# turbidity_sensor_module.net
KiCad netlist of a schematic drawn in EAGLE
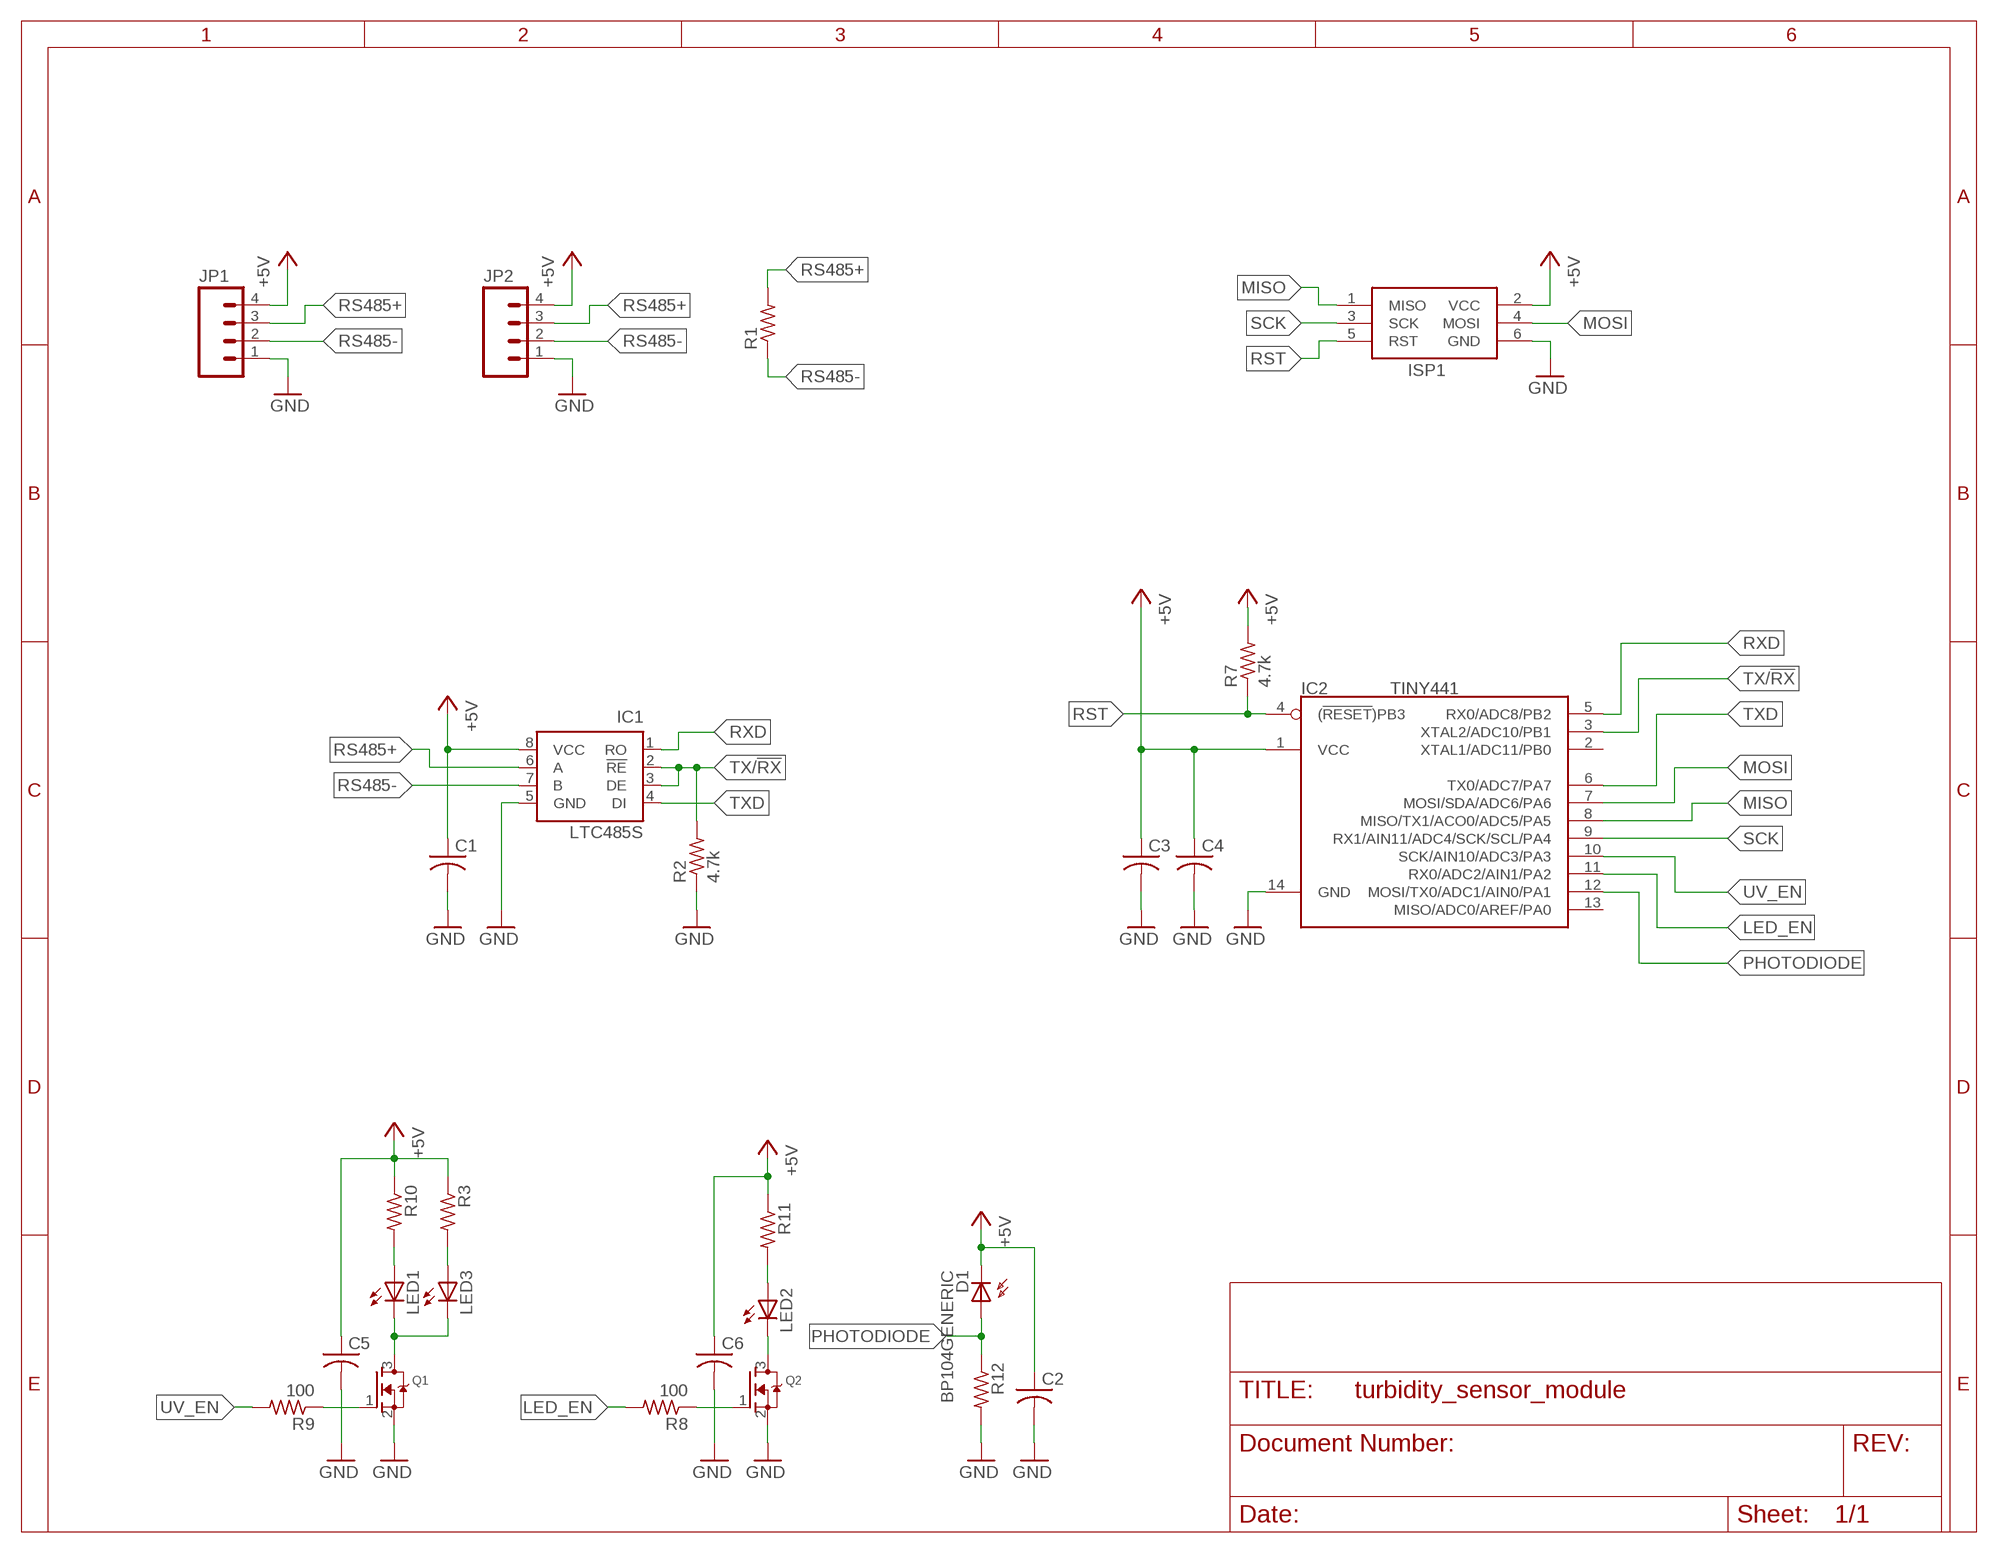
[diagram p0: schematic, sheet 1]

(export (version "E")
  (design (tool "Eeschema 10.0.6"))
  (components
    (comp (ref "C1")
      (value "C-USC1206")
      (footprint "eagle-import:C1206")
      (libsource (lib "eagle-import") (part "C-USC1206"))
    )
    (comp (ref "C2")
      (value "C-USC1206")
      (footprint "eagle-import:C1206")
      (libsource (lib "eagle-import") (part "C-USC1206"))
    )
    (comp (ref "C3")
      (value "C-USC1206")
      (footprint "eagle-import:C1206")
      (libsource (lib "eagle-import") (part "C-USC1206"))
    )
    (comp (ref "C4")
      (value "C-USC1206")
      (footprint "eagle-import:C1206")
      (libsource (lib "eagle-import") (part "C-USC1206"))
    )
    (comp (ref "C5")
      (value "C-USC1206")
      (footprint "eagle-import:C1206")
      (libsource (lib "eagle-import") (part "C-USC1206"))
    )
    (comp (ref "C6")
      (value "C-USC1206")
      (footprint "eagle-import:C1206")
      (libsource (lib "eagle-import") (part "C-USC1206"))
    )
    (comp (ref "D1")
      (value "BP104GENERIC")
      (footprint "eagle-import:PHOTODIODE")
      (libsource (lib "eagle-import") (part "BP104GENERIC"))
    )
    (comp (ref "IC1")
      (value "LTC485S")
      (footprint "eagle-import:SOIC8")
      (libsource (lib "eagle-import") (part "LTC485S"))
    )
    (comp (ref "IC2")
      (value "TINY441")
      (footprint "eagle-import:SOIC14")
      (libsource (lib "eagle-import") (part "TINY441"))
    )
    (comp (ref "ISP1")
      (value "AVRISP-6")
      (footprint "eagle-import:AVRISP")
      (libsource (lib "eagle-import") (part "AVRISP-6"))
    )
    (comp (ref "JP1")
      (value "M04LONGPADS")
      (footprint "eagle-import:1X04_LONGPADS")
      (libsource (lib "eagle-import") (part "M04LONGPADS"))
    )
    (comp (ref "JP2")
      (value "M04LONGPADS")
      (footprint "eagle-import:1X04_LONGPADS")
      (libsource (lib "eagle-import") (part "M04LONGPADS"))
    )
    (comp (ref "LED1")
      (value "LED5MM")
      (footprint "eagle-import:LED5MM")
      (libsource (lib "eagle-import") (part "LED5MM"))
    )
    (comp (ref "LED2")
      (value "LED5MM")
      (footprint "eagle-import:LED5MM")
      (libsource (lib "eagle-import") (part "LED5MM"))
    )
    (comp (ref "LED3")
      (value "LED5MM")
      (footprint "eagle-import:LED5MM")
      (libsource (lib "eagle-import") (part "LED5MM"))
    )
    (comp (ref "Q1")
      (value "MOSFET-NREFLOW")
      (footprint "eagle-import:SOT23")
      (libsource (lib "eagle-import") (part "MOSFET-NREFLOW"))
    )
    (comp (ref "Q2")
      (value "MOSFET-NREFLOW")
      (footprint "eagle-import:SOT23")
      (libsource (lib "eagle-import") (part "MOSFET-NREFLOW"))
    )
    (comp (ref "R1")
      (value "R-US_R1206")
      (footprint "eagle-import:R1206")
      (libsource (lib "eagle-import") (part "R-US_R1206"))
    )
    (comp (ref "R2")
      (value "4.7k")
      (footprint "eagle-import:R1206")
      (libsource (lib "eagle-import") (part "R-US_R1206"))
    )
    (comp (ref "R3")
      (value "R-US_R1206")
      (footprint "eagle-import:R1206")
      (libsource (lib "eagle-import") (part "R-US_R1206"))
    )
    (comp (ref "R7")
      (value "4.7k")
      (footprint "eagle-import:R1206")
      (libsource (lib "eagle-import") (part "R-US_R1206"))
    )
    (comp (ref "R8")
      (value "100")
      (footprint "eagle-import:R1206")
      (libsource (lib "eagle-import") (part "R-US_R1206"))
    )
    (comp (ref "R9")
      (value "100")
      (footprint "eagle-import:R1206")
      (libsource (lib "eagle-import") (part "R-US_R1206"))
    )
    (comp (ref "R10")
      (value "R-US_R1206")
      (footprint "eagle-import:R1206")
      (libsource (lib "eagle-import") (part "R-US_R1206"))
    )
    (comp (ref "R11")
      (value "R-US_R1206")
      (footprint "eagle-import:R1206")
      (libsource (lib "eagle-import") (part "R-US_R1206"))
    )
    (comp (ref "R12")
      (value "R-US_R1206")
      (footprint "eagle-import:R1206")
      (libsource (lib "eagle-import") (part "R-US_R1206"))
    )
  )
  (nets
    (net (code "1") (name "+5V") (class "Default")
      (node (ref "C1") (pin "1") (pinfunction "1_1") (pintype "passive"))
      (node (ref "C2") (pin "1") (pinfunction "1_1") (pintype "passive"))
      (node (ref "C3") (pin "1") (pinfunction "1_1") (pintype "passive"))
      (node (ref "C4") (pin "1") (pinfunction "1_1") (pintype "passive"))
      (node (ref "C5") (pin "1") (pinfunction "1_1") (pintype "passive"))
      (node (ref "C6") (pin "1") (pinfunction "1_1") (pintype "passive"))
      (node (ref "D1") (pin "K") (pinfunction "C_K") (pintype "passive"))
      (node (ref "IC1") (pin "8") (pinfunction "VCC_8") (pintype "input"))
      (node (ref "IC2") (pin "1") (pinfunction "VCC_1") (pintype "power_in"))
      (node (ref "ISP1") (pin "2") (pinfunction "VCC_2") (pintype "power_in"))
      (node (ref "JP1") (pin "4") (pinfunction "4_4") (pintype "passive"))
      (node (ref "JP2") (pin "4") (pinfunction "4_4") (pintype "passive"))
      (node (ref "R10") (pin "1") (pinfunction "1_1") (pintype "passive"))
      (node (ref "R11") (pin "1") (pinfunction "1_1") (pintype "passive"))
      (node (ref "R3") (pin "1") (pinfunction "1_1") (pintype "passive"))
      (node (ref "R7") (pin "2") (pinfunction "2_2") (pintype "passive"))
    )
    (net (code "2") (name "/TX{slash}~{RX}") (class "Default")
      (node (ref "IC1") (pin "2") (pinfunction "~{RE}_2") (pintype "input"))
      (node (ref "IC1") (pin "3") (pinfunction "DE_3") (pintype "input"))
      (node (ref "IC2") (pin "3") (pinfunction "XTAL2/ADC10/PB1_3") (pintype "bidirectional"))
      (node (ref "R2") (pin "2") (pinfunction "2_2") (pintype "passive"))
    )
    (net (code "3") (name "GND") (class "Default")
      (node (ref "C1") (pin "2") (pinfunction "2_2") (pintype "passive"))
      (node (ref "C2") (pin "2") (pinfunction "2_2") (pintype "passive"))
      (node (ref "C3") (pin "2") (pinfunction "2_2") (pintype "passive"))
      (node (ref "C4") (pin "2") (pinfunction "2_2") (pintype "passive"))
      (node (ref "C5") (pin "2") (pinfunction "2_2") (pintype "passive"))
      (node (ref "C6") (pin "2") (pinfunction "2_2") (pintype "passive"))
      (node (ref "IC1") (pin "5") (pinfunction "GND_5") (pintype "input"))
      (node (ref "IC2") (pin "14") (pinfunction "GND_14") (pintype "power_in"))
      (node (ref "ISP1") (pin "6") (pinfunction "GND_6") (pintype "power_in"))
      (node (ref "JP1") (pin "1") (pinfunction "1_1") (pintype "passive"))
      (node (ref "JP2") (pin "1") (pinfunction "1_1") (pintype "passive"))
      (node (ref "Q1") (pin "2") (pinfunction "S_2") (pintype "bidirectional"))
      (node (ref "Q2") (pin "2") (pinfunction "S_2") (pintype "bidirectional"))
      (node (ref "R12") (pin "2") (pinfunction "2_2") (pintype "passive"))
      (node (ref "R2") (pin "1") (pinfunction "1_1") (pintype "passive"))
    )
    (net (code "4") (name "LED_EN") (class "Default")
      (node (ref "IC2") (pin "11") (pinfunction "RX0/ADC2/AIN1/PA2_11") (pintype "bidirectional"))
      (node (ref "R8") (pin "2") (pinfunction "2_2") (pintype "passive"))
    )
    (net (code "5") (name "MISO") (class "Default")
      (node (ref "IC2") (pin "8") (pinfunction "MISO/TX1/ACO0/ADC5/PA5_8") (pintype "bidirectional"))
      (node (ref "ISP1") (pin "1") (pinfunction "MISO_1") (pintype "input"))
    )
    (net (code "6") (name "MOSI") (class "Default")
      (node (ref "IC2") (pin "7") (pinfunction "MOSI/SDA/ADC6/PA6_7") (pintype "bidirectional"))
      (node (ref "ISP1") (pin "4") (pinfunction "MOSI_4") (pintype "output"))
    )
    (net (code "7") (name "Net-(LED1-C)") (class "Default")
      (node (ref "LED1") (pin "K") (pinfunction "C_K") (pintype "passive"))
      (node (ref "LED3") (pin "K") (pinfunction "C_K") (pintype "passive"))
      (node (ref "Q1") (pin "3") (pinfunction "D_3") (pintype "bidirectional"))
    )
    (net (code "8") (name "Net-(LED1-PadA)") (class "Default")
      (node (ref "LED1") (pin "A") (pinfunction "A_A") (pintype "passive"))
      (node (ref "R10") (pin "2") (pinfunction "2_2") (pintype "passive"))
    )
    (net (code "9") (name "Net-(LED2-C)") (class "Default")
      (node (ref "LED2") (pin "K") (pinfunction "C_K") (pintype "passive"))
      (node (ref "Q2") (pin "3") (pinfunction "D_3") (pintype "bidirectional"))
    )
    (net (code "10") (name "Net-(LED2-PadA)") (class "Default")
      (node (ref "LED2") (pin "A") (pinfunction "A_A") (pintype "passive"))
      (node (ref "R11") (pin "2") (pinfunction "2_2") (pintype "passive"))
    )
    (net (code "11") (name "Net-(LED3-PadA)") (class "Default")
      (node (ref "LED3") (pin "A") (pinfunction "A_A") (pintype "passive"))
      (node (ref "R3") (pin "2") (pinfunction "2_2") (pintype "passive"))
    )
    (net (code "12") (name "Net-(Q1-G)") (class "Default")
      (node (ref "Q1") (pin "1") (pinfunction "G_1") (pintype "bidirectional"))
      (node (ref "R9") (pin "1") (pinfunction "1_1") (pintype "passive"))
    )
    (net (code "13") (name "Net-(Q2-G)") (class "Default")
      (node (ref "Q2") (pin "1") (pinfunction "G_1") (pintype "bidirectional"))
      (node (ref "R8") (pin "1") (pinfunction "1_1") (pintype "passive"))
    )
    (net (code "14") (name "PHOTODIODE") (class "Default")
      (node (ref "D1") (pin "A") (pinfunction "A_A") (pintype "passive"))
      (node (ref "IC2") (pin "12") (pinfunction "MOSI/TX0/ADC1/AIN0/PA1_12") (pintype "bidirectional"))
      (node (ref "R12") (pin "1") (pinfunction "1_1") (pintype "passive"))
    )
    (net (code "15") (name "RS485+") (class "Default")
      (node (ref "IC1") (pin "6") (pinfunction "A_6") (pintype "bidirectional"))
      (node (ref "JP1") (pin "3") (pinfunction "3_3") (pintype "passive"))
      (node (ref "JP2") (pin "3") (pinfunction "3_3") (pintype "passive"))
      (node (ref "R1") (pin "2") (pinfunction "2_2") (pintype "passive"))
    )
    (net (code "16") (name "RS485-") (class "Default")
      (node (ref "IC1") (pin "7") (pinfunction "B_7") (pintype "bidirectional"))
      (node (ref "JP1") (pin "2") (pinfunction "2_2") (pintype "passive"))
      (node (ref "JP2") (pin "2") (pinfunction "2_2") (pintype "passive"))
      (node (ref "R1") (pin "1") (pinfunction "1_1") (pintype "passive"))
    )
    (net (code "17") (name "RST") (class "Default")
      (node (ref "IC2") (pin "4") (pinfunction "(~{RESET})PB3_4") (pintype "bidirectional"))
      (node (ref "ISP1") (pin "5") (pinfunction "RST_5") (pintype "output"))
      (node (ref "R7") (pin "1") (pinfunction "1_1") (pintype "passive"))
    )
    (net (code "18") (name "RXD") (class "Default")
      (node (ref "IC1") (pin "1") (pinfunction "RO_1") (pintype "output"))
      (node (ref "IC2") (pin "5") (pinfunction "RX0/ADC8/PB2_5") (pintype "bidirectional"))
    )
    (net (code "19") (name "SCK") (class "Default")
      (node (ref "IC2") (pin "9") (pinfunction "RX1/AIN11/ADC4/SCK/SCL/PA4_9") (pintype "bidirectional"))
      (node (ref "ISP1") (pin "3") (pinfunction "SCK_3") (pintype "output"))
    )
    (net (code "20") (name "TXD") (class "Default")
      (node (ref "IC1") (pin "4") (pinfunction "DI_4") (pintype "input"))
      (node (ref "IC2") (pin "6") (pinfunction "TX0/ADC7/PA7_6") (pintype "bidirectional"))
    )
    (net (code "21") (name "UV_EN") (class "Default")
      (node (ref "IC2") (pin "10") (pinfunction "SCK/AIN10/ADC3/PA3_10") (pintype "bidirectional"))
      (node (ref "R9") (pin "2") (pinfunction "2_2") (pintype "passive"))
    )
    (net (code "22") (name "unconnected-(IC2-MISO{slash}ADC0{slash}AREF{slash}PA0-Pad13)") (class "Default")
      (node (ref "IC2") (pin "13") (pinfunction "MISO/ADC0/AREF/PA0_13") (pintype "bidirectional"))
    )
    (net (code "23") (name "unconnected-(IC2-XTAL1{slash}ADC11{slash}PB0-Pad2)") (class "Default")
      (node (ref "IC2") (pin "2") (pinfunction "XTAL1/ADC11/PB0_2") (pintype "bidirectional"))
    )
  )
)
